# Power.net
KiCad netlist of a schematic drawn in Altium Designer
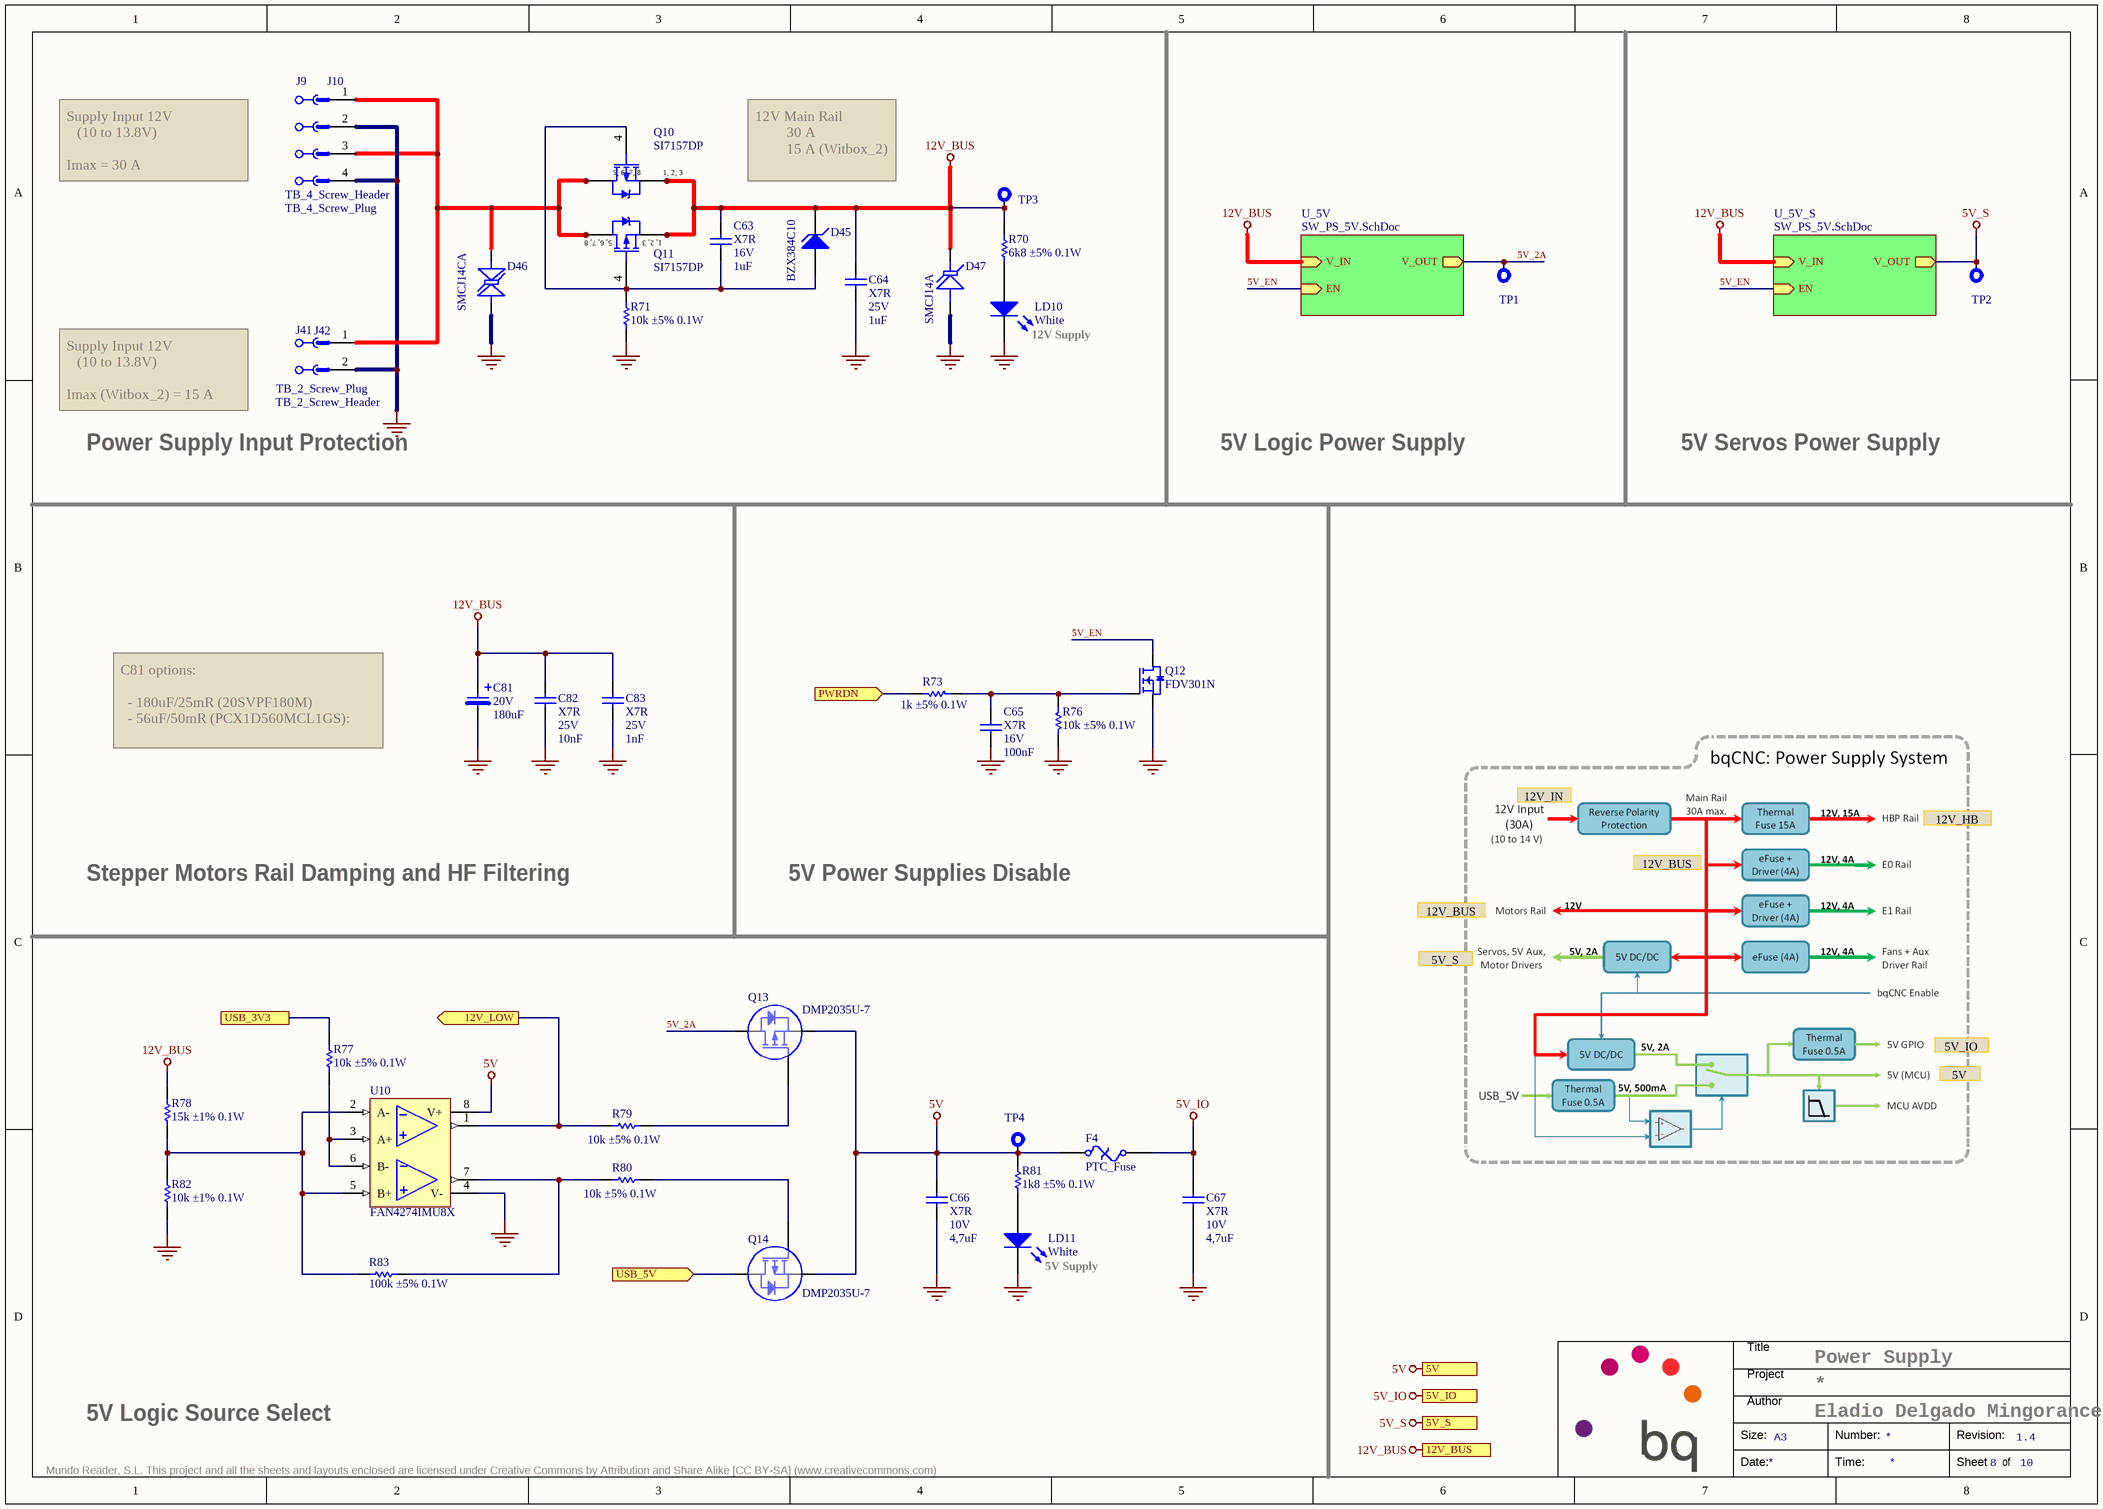
[diagram p0: Power.SchDoc]

(export (version "E")
  (design (tool "Eeschema 10.0.6"))
  (components
    (comp (ref "C63")
      (value "Capacitor")
      (footprint "C0603")
      (fields
        (field (name "DIELECTRIC") "X7R")
        (field (name "VOLTAGE") "16V")
        (field (name "CAPACITANCE") "1uF")
        (field (name "PART NUMBER") "C0603_1uF_16V_±10%_X7R")
        (field (name "TOLERANCE") "±10%")
        (field (name "MANUFACTURER") "TDK")
      )
      (libsource (lib "Pasives_Capacitor_SMD") (part "Capacitor"))
    )
    (comp (ref "C64")
      (value "Capacitor")
      (footprint "C0805")
      (fields
        (field (name "DIELECTRIC") "X7R")
        (field (name "VOLTAGE") "25V")
        (field (name "CAPACITANCE") "1uF")
        (field (name "PART NUMBER") "C0805_1uF_25V_X7R")
        (field (name "TOLERANCE") "±10%")
        (field (name "MANUFACTURER") "TDK")
      )
      (libsource (lib "Pasives_Capacitor_SMD") (part "Capacitor"))
    )
    (comp (ref "C65")
      (value "Capacitor")
      (footprint "C0603")
      (fields
        (field (name "DIELECTRIC") "X7R")
        (field (name "VOLTAGE") "16V")
        (field (name "CAPACITANCE") "100nF")
        (field (name "PART NUMBER") "C0603_100nF_16V_±10%")
        (field (name "TOLERANCE") "±10%")
        (field (name "MANUFACTURER") "Kemet")
      )
      (libsource (lib "Pasives_Capacitor_SMD") (part "Capacitor"))
    )
    (comp (ref "C66")
      (value "Capacitor")
      (footprint "C0805")
      (fields
        (field (name "DIELECTRIC") "X7R")
        (field (name "VOLTAGE") "10V")
        (field (name "CAPACITANCE") "4,7uF")
        (field (name "PART NUMBER") "C0805_4,7uF_10V_X7R")
        (field (name "TOLERANCE") "±10%")
        (field (name "MANUFACTURER") "TDK")
      )
      (libsource (lib "Pasives_Capacitor_SMD") (part "Capacitor"))
    )
    (comp (ref "C67")
      (value "Capacitor")
      (footprint "C0805")
      (fields
        (field (name "DIELECTRIC") "X7R")
        (field (name "VOLTAGE") "10V")
        (field (name "CAPACITANCE") "4,7uF")
        (field (name "PART NUMBER") "C0805_4,7uF_10V_X7R")
        (field (name "TOLERANCE") "±10%")
        (field (name "MANUFACTURER") "TDK")
      )
      (libsource (lib "Pasives_Capacitor_SMD") (part "Capacitor"))
    )
    (comp (ref "C81")
      (value "Electrolytic")
      (footprint "CASE_E7")
      (description "Capacitor, Electrolytic, SMD")
      (fields
        (field (name "VOLTAGE") "20V")
        (field (name "CAPACITANCE") "180uF")
        (field (name "PART NUMBER") "Cap_Al_180uF_20V")
        (field (name "MANUFACTURER") "Panasonic")
      )
      (libsource (lib "Pasives_Electrolytic_SMD") (part "Electrolytic"))
    )
    (comp (ref "C82")
      (value "Capacitor")
      (footprint "C0603")
      (description "Capacitor SMD")
      (fields
        (field (name "DIELECTRIC") "X7R")
        (field (name "VOLTAGE") "25V")
        (field (name "CAPACITANCE") "10nF")
        (field (name "PART NUMBER") "C0603_10nF_25V_±10%")
        (field (name "TOLERANCE") "±10%")
      )
      (libsource (lib "Pasives_Capacitor_SMD") (part "Capacitor"))
    )
    (comp (ref "C83")
      (value "Capacitor")
      (footprint "C0603")
      (description "Capacitor SMD")
      (fields
        (field (name "DIELECTRIC") "X7R")
        (field (name "VOLTAGE") "25V")
        (field (name "CAPACITANCE") "1nF")
        (field (name "PART NUMBER") "C0603_1nF_25V_±10%")
        (field (name "TOLERANCE") "±10%")
      )
      (libsource (lib "Pasives_Capacitor_SMD") (part "Capacitor"))
    )
    (comp (ref "D45")
      (value "BZX384C10")
      (footprint "SOD323")
      (description "Diode Zener")
      (fields (field (name "TOLERANCE") "0,05") (field (name "POWER") "200mW"))
      (libsource (lib "Semiconductors_Diodes") (part "Zener"))
    )
    (comp (ref "D46")
      (value "SMCJ14CA")
      (footprint "DO-214AB-SMC")
      (description "Transient Suppression Diodes Bidirectional")
      (fields (field (name "PART NUMBER") "TVS 14V Bidir SMC") (field (name "VOLTAGE") "14V"))
      (libsource (lib "Protection") (part "Zener_Bidir_TVS"))
    )
    (comp (ref "D47")
      (value "SMCJ14A")
      (footprint "DO-214AB-SMC")
      (description "Transient Suppression Diodes")
      (fields (field (name "PART NUMBER") "TVS 14V SMC") (field (name "VOLTAGE") "14V"))
      (libsource (lib "Protection") (part "Zener_TVS"))
    )
    (comp (ref "F4")
      (value "PTC_Fuse")
      (footprint "F1812")
      (description "PTC Resettable Fuse")
      (fields (field (name "PART NUMBER") "FUSE 0.5A 15V") (field (name "VOLTAGE") "15V"))
      (libsource (lib "Protection") (part "PTC_Fuse"))
    )
    (comp (ref "J9")
      (value "TB_4_Screw_Plug")
      (footprint "TB_RA_4_5.08_Plug")
      (description "Connector, Plugable Terminal  Block  - Plug 4p")
      (fields (field (name "PART NUMBER") "TB_4_RA_Plug_5.08") (field (name "MANUFACTURER") "Molex"))
      (libsource (lib "Connectors_TB") (part "TB_4_Screw_Plug"))
    )
    (comp (ref "J10")
      (value "TB_4_Screw_Header")
      (footprint "TB_RA_4_5.08")
      (description "Connector, Plugable Terminal  Block  - Header 4p")
      (fields (field (name "PART NUMBER") "TB_4_RA_Header_5.08") (field (name "MANUFACTURER") "Molex"))
      (libsource (lib "Connectors_TB") (part "TB_4_Screw_Header"))
    )
    (comp (ref "J41")
      (value "TB_2_Screw_Plug")
      (footprint "TB_RA_2_5.08_Plug")
      (description "Connector, Plugable Terminal  Block  - Plug 2p")
      (fields (field (name "PART NUMBER") "TB_2_RA_Plug_5.08") (field (name "MANUFACTURER") "Molex"))
      (libsource (lib "Connectors_TB") (part "TB_2_Screw_Plug"))
    )
    (comp (ref "J42")
      (value "TB_2_Screw_Header")
      (footprint "TB_RA_2_5.08")
      (description "Connector, Plugable Terminal  Block  - Header 2p")
      (fields (field (name "PART NUMBER") "TB_2_RA_Header_5.08") (field (name "MANUFACTURER") "Molex"))
      (libsource (lib "Connectors_TB") (part "TB_2_Screw_Header"))
    )
    (comp (ref "LD10")
      (value "White")
      (footprint "LED0603")
      (description "LED")
      (fields (field (name "PART NUMBER") "LW Q38G-Q2R3") (field (name "MANUFACTURER") "OSRAM Opto"))
      (libsource (lib "Optoelectronics") (part "LED"))
    )
    (comp (ref "LD11")
      (value "White")
      (footprint "LED0603")
      (description "LED")
      (fields (field (name "PART NUMBER") "LW Q38G-Q2R3") (field (name "MANUFACTURER") "OSRAM Opto"))
      (libsource (lib "Optoelectronics") (part "LED"))
    )
    (comp (ref "Q10")
      (value "SI7157DP")
      (footprint "AO_DFN5x6")
      (description "PFET Power SO8")
      (fields (field (name "MANUFACTURER") "Vishay"))
      (libsource (lib "Semiconductors_Transistors") (part "P-MOSFET Power SO8"))
    )
    (comp (ref "Q11")
      (value "SI7157DP")
      (footprint "AO_DFN5x6")
      (description "PFET Power SO8")
      (fields (field (name "MANUFACTURER") "Vishay"))
      (libsource (lib "Semiconductors_Transistors") (part "P-MOSFET Power SO8"))
    )
    (comp (ref "Q12")
      (value "FDV301N")
      (footprint "SOT23-3")
      (description "Mosfet Channel N Enhancement Mode")
      (fields (field (name "MANUFACTURER") "Fairchild Semiconductor"))
      (libsource (lib "Semiconductors_Transistors") (part "Mosfet_N"))
    )
    (comp (ref "Q13")
      (value "DMP2035U-7")
      (footprint "SOT23-3")
      (description "Mosfet Channel P Enhancement Mode")
      (fields (field (name "PART NUMBER") "DMP2035U") (field (name "MANUFACTURER") "Diodes Incorporated"))
      (libsource (lib "Semiconductors_Transistors") (part "Mosfet_P"))
    )
    (comp (ref "Q14")
      (value "DMP2035U-7")
      (footprint "SOT23-3")
      (description "Mosfet Channel P Enhancement Mode")
      (fields (field (name "PART NUMBER") "DMP2035U") (field (name "MANUFACTURER") "Diodes Incorporated"))
      (libsource (lib "Semiconductors_Transistors") (part "Mosfet_P"))
    )
    (comp (ref "R70")
      (value "6k8 ±5% 0.1W")
      (footprint "R0603")
      (description "Resistor, SMD")
      (fields (field (name "TOLERANCE") "±5%") (field (name "POWER") "0.1W"))
      (libsource (lib "Pasives_Resistor_SMD") (part "Resistor"))
    )
    (comp (ref "R71")
      (value "10k ±5% 0.1W")
      (footprint "R0603")
      (description "Resistor")
      (fields (field (name "TOLERANCE") "±5%") (field (name "POWER") "0.1W"))
      (libsource (lib "Pasives_Resistor_SMD") (part "Resistor"))
    )
    (comp (ref "R73")
      (value "1k ±5% 0.1W")
      (footprint "R0603")
      (description "Resistor")
      (fields (field (name "TOLERANCE") "±5%") (field (name "POWER") "0.1W"))
      (libsource (lib "Pasives_Resistor_SMD") (part "Resistor"))
    )
    (comp (ref "R76")
      (value "10k ±5% 0.1W")
      (footprint "R0603")
      (description "Resistor")
      (fields (field (name "TOLERANCE") "±5%") (field (name "POWER") "0.1W"))
      (libsource (lib "Pasives_Resistor_SMD") (part "Resistor"))
    )
    (comp (ref "R77")
      (value "10k ±5% 0.1W")
      (footprint "R0603")
      (description "Resistor")
      (fields (field (name "TOLERANCE") "±5%") (field (name "POWER") "0.1W"))
      (libsource (lib "Pasives_Resistor_SMD") (part "Resistor"))
    )
    (comp (ref "R78")
      (value "15k ±1% 0.1W")
      (footprint "R0603")
      (description "Resistor")
      (fields (field (name "TOLERANCE") "±1%") (field (name "POWER") "0.1W"))
      (libsource (lib "Pasives_Resistor_SMD") (part "Resistor"))
    )
    (comp (ref "R79")
      (value "10k ±5% 0.1W")
      (footprint "R0603")
      (description "Resistor")
      (fields (field (name "TOLERANCE") "±5%") (field (name "POWER") "0.1W"))
      (libsource (lib "Pasives_Resistor_SMD") (part "Resistor"))
    )
    (comp (ref "R80")
      (value "10k ±5% 0.1W")
      (footprint "R0603")
      (description "Resistor")
      (fields (field (name "TOLERANCE") "±5%") (field (name "POWER") "0.1W"))
      (libsource (lib "Pasives_Resistor_SMD") (part "Resistor"))
    )
    (comp (ref "R81")
      (value "1k8 ±5% 0.1W")
      (footprint "R0603")
      (description "Resistor, SMD")
      (fields (field (name "TOLERANCE") "±5%") (field (name "POWER") "0.1W"))
      (libsource (lib "Pasives_Resistor_SMD") (part "Resistor"))
    )
    (comp (ref "R82")
      (value "10k ±1% 0.1W")
      (footprint "R0603")
      (description "Resistor")
      (fields (field (name "TOLERANCE") "±1%") (field (name "POWER") "0.1W"))
      (libsource (lib "Pasives_Resistor_SMD") (part "Resistor"))
    )
    (comp (ref "R83")
      (value "100k ±5% 0.1W")
      (footprint "R0603")
      (description "Resistor")
      (fields (field (name "TOLERANCE") "±5%") (field (name "POWER") "0.1W"))
      (libsource (lib "Pasives_Resistor_SMD") (part "Resistor"))
    )
    (comp (ref "TP1")
      (value "Testpoint")
      (footprint "TP_SMD_1mm")
      (fields (field (name "PART NUMBER") "TP_SMD_1mm"))
      (libsource (lib "Miscelanea") (part "Testpoint"))
    )
    (comp (ref "TP2")
      (value "Testpoint")
      (footprint "TP_SMD_1mm")
      (fields (field (name "PART NUMBER") "TP_SMD_1mm"))
      (libsource (lib "Miscelanea") (part "Testpoint"))
    )
    (comp (ref "TP3")
      (value "Testpoint")
      (footprint "TP_SMD_1mm")
      (fields (field (name "PART NUMBER") "TP_SMD_1mm"))
      (libsource (lib "Miscelanea") (part "Testpoint"))
    )
    (comp (ref "TP4")
      (value "Testpoint")
      (footprint "TP_SMD_1mm")
      (fields (field (name "PART NUMBER") "TP_SMD_1mm"))
      (libsource (lib "Miscelanea") (part "Testpoint"))
    )
    (comp (ref "U10")
      (value "FAN4274IMU8X")
      (footprint "VSSOP8")
      (description "Operational Amplifier Dual 3.7MHz")
      (fields (field (name "PART NUMBER") "FAN4274") (field (name "MANUFACTURER") "Fairchild Semiconductor"))
      (libsource (lib "Semiconductors_OA") (part "FAN4274"))
    )
  )
  (nets
    (net (code "1") (name "/5V_2A") (class "Default")
      (node (ref "Q13") (pin "3") (pinfunction "D_3") (pintype "passive"))
      (node (ref "TP1") (pin "1") (pinfunction "1_1") (pintype "passive"))
    )
    (net (code "2") (name "/5V_EN") (class "Default")
      (node (ref "Q12") (pin "3") (pinfunction "D_3") (pintype "passive"))
    )
    (net (code "3") (name "/12V_LOW") (class "Default")
      (node (ref "R79") (pin "2") (pinfunction "2_2") (pintype "passive"))
      (node (ref "U10") (pin "1") (pinfunction "OutA_1") (pintype "output"))
    )
    (net (code "4") (name "/PWRDN") (class "Default")
      (node (ref "R73") (pin "2") (pinfunction "2_2") (pintype "passive"))
    )
    (net (code "5") (name "/USB_3V3") (class "Default")
      (node (ref "R77") (pin "2") (pinfunction "2_2") (pintype "passive"))
    )
    (net (code "6") (name "/USB_5V") (class "Default")
      (node (ref "Q14") (pin "3") (pinfunction "D_3") (pintype "passive"))
    )
    (net (code "7") (name "5V") (class "Default")
      (node (ref "C66") (pin "2") (pinfunction "2_2") (pintype "passive"))
      (node (ref "F4") (pin "1") (pinfunction "1_1") (pintype "passive"))
      (node (ref "Q13") (pin "2") (pinfunction "S_2") (pintype "passive"))
      (node (ref "Q14") (pin "2") (pinfunction "S_2") (pintype "passive"))
      (node (ref "R81") (pin "2") (pinfunction "2_2") (pintype "passive"))
      (node (ref "TP4") (pin "1") (pinfunction "1_1") (pintype "passive"))
      (node (ref "U10") (pin "8") (pinfunction "V+_8") (pintype "power_in"))
    )
    (net (code "8") (name "5V_IO") (class "Default")
      (node (ref "C67") (pin "2") (pinfunction "2_2") (pintype "passive"))
      (node (ref "F4") (pin "2") (pinfunction "2_2") (pintype "passive"))
    )
    (net (code "9") (name "5V_S") (class "Default")
      (node (ref "TP2") (pin "1") (pinfunction "1_1") (pintype "passive"))
    )
    (net (code "10") (name "12V_BUS") (class "Default")
      (node (ref "C63") (pin "2") (pinfunction "2_2") (pintype "passive"))
      (node (ref "C64") (pin "2") (pinfunction "2_2") (pintype "passive"))
      (node (ref "C81") (pin "1") (pinfunction "1_1") (pintype "passive"))
      (node (ref "C82") (pin "2") (pinfunction "2_2") (pintype "passive"))
      (node (ref "C83") (pin "2") (pinfunction "2_2") (pintype "passive"))
      (node (ref "D45") (pin "k") (pinfunction "K_k") (pintype "passive"))
      (node (ref "D47") (pin "K") (pinfunction "K_K") (pintype "passive"))
      (node (ref "Q10") (pin "1") (pinfunction "S_1") (pintype "passive"))
      (node (ref "Q10") (pin "2") (pinfunction "S_2") (pintype "passive"))
      (node (ref "Q10") (pin "3") (pinfunction "S_3") (pintype "passive"))
      (node (ref "Q11") (pin "1") (pinfunction "S_1") (pintype "passive"))
      (node (ref "Q11") (pin "2") (pinfunction "S_2") (pintype "passive"))
      (node (ref "Q11") (pin "3") (pinfunction "S_3") (pintype "passive"))
      (node (ref "R70") (pin "2") (pinfunction "2_2") (pintype "passive"))
      (node (ref "R78") (pin "2") (pinfunction "2_2") (pintype "passive"))
      (node (ref "TP3") (pin "1") (pinfunction "1_1") (pintype "passive"))
    )
    (net (code "11") (name "GND") (class "Default")
      (node (ref "C64") (pin "1") (pinfunction "1_1") (pintype "passive"))
      (node (ref "C65") (pin "1") (pinfunction "1_1") (pintype "passive"))
      (node (ref "C66") (pin "1") (pinfunction "1_1") (pintype "passive"))
      (node (ref "C67") (pin "1") (pinfunction "1_1") (pintype "passive"))
      (node (ref "C81") (pin "2") (pinfunction "2_2") (pintype "passive"))
      (node (ref "C82") (pin "1") (pinfunction "1_1") (pintype "passive"))
      (node (ref "C83") (pin "1") (pinfunction "1_1") (pintype "passive"))
      (node (ref "D46") (pin "A") (pinfunction "A_A") (pintype "passive"))
      (node (ref "D47") (pin "A") (pinfunction "A_A") (pintype "passive"))
      (node (ref "J10") (pin "2") (pinfunction "2_2") (pintype "passive"))
      (node (ref "J10") (pin "4") (pinfunction "4_4") (pintype "passive"))
      (node (ref "J42") (pin "2") (pinfunction "2_2") (pintype "passive"))
      (node (ref "LD10") (pin "K") (pinfunction "K_K") (pintype "passive"))
      (node (ref "LD11") (pin "K") (pinfunction "K_K") (pintype "passive"))
      (node (ref "Q12") (pin "2") (pinfunction "S_2") (pintype "passive"))
      (node (ref "R71") (pin "1") (pinfunction "1_1") (pintype "passive"))
      (node (ref "R76") (pin "2") (pinfunction "2_2") (pintype "passive"))
      (node (ref "R82") (pin "1") (pinfunction "1_1") (pintype "passive"))
      (node (ref "U10") (pin "4") (pinfunction "V-_4") (pintype "power_in"))
    )
    (net (code "12") (name "Net-(D46-PadK)") (class "Default")
      (node (ref "D46") (pin "K") (pinfunction "K_K") (pintype "passive"))
      (node (ref "J10") (pin "1") (pinfunction "1_1") (pintype "passive"))
      (node (ref "J10") (pin "3") (pinfunction "3_3") (pintype "passive"))
      (node (ref "J42") (pin "1") (pinfunction "1_1") (pintype "passive"))
      (node (ref "Q10") (pin "5") (pinfunction "D_5") (pintype "passive"))
      (node (ref "Q10") (pin "6") (pinfunction "D_6") (pintype "passive"))
      (node (ref "Q10") (pin "7") (pinfunction "D_7") (pintype "passive"))
      (node (ref "Q10") (pin "8") (pinfunction "D_8") (pintype "passive"))
      (node (ref "Q11") (pin "5") (pinfunction "D_5") (pintype "passive"))
      (node (ref "Q11") (pin "6") (pinfunction "D_6") (pintype "passive"))
      (node (ref "Q11") (pin "7") (pinfunction "D_7") (pintype "passive"))
      (node (ref "Q11") (pin "8") (pinfunction "D_8") (pintype "passive"))
    )
    (net (code "13") (name "Net-(LD10-PadA)") (class "Default")
      (node (ref "LD10") (pin "A") (pinfunction "A_A") (pintype "passive"))
      (node (ref "R70") (pin "1") (pinfunction "1_1") (pintype "passive"))
    )
    (net (code "14") (name "Net-(LD11-PadA)") (class "Default")
      (node (ref "LD11") (pin "A") (pinfunction "A_A") (pintype "passive"))
      (node (ref "R81") (pin "1") (pinfunction "1_1") (pintype "passive"))
    )
    (net (code "15") (name "Net-(Q10-G)") (class "Default")
      (node (ref "C63") (pin "1") (pinfunction "1_1") (pintype "passive"))
      (node (ref "D45") (pin "A") (pinfunction "A_A") (pintype "passive"))
      (node (ref "Q10") (pin "4") (pinfunction "G_4") (pintype "passive"))
      (node (ref "Q11") (pin "4") (pinfunction "G_4") (pintype "passive"))
      (node (ref "R71") (pin "2") (pinfunction "2_2") (pintype "passive"))
    )
    (net (code "16") (name "Net-(Q12-G)") (class "Default")
      (node (ref "C65") (pin "2") (pinfunction "2_2") (pintype "passive"))
      (node (ref "Q12") (pin "1") (pinfunction "G_1") (pintype "passive"))
      (node (ref "R73") (pin "1") (pinfunction "1_1") (pintype "passive"))
      (node (ref "R76") (pin "1") (pinfunction "1_1") (pintype "passive"))
    )
    (net (code "17") (name "Net-(Q13-G)") (class "Default")
      (node (ref "Q13") (pin "1") (pinfunction "G_1") (pintype "passive"))
      (node (ref "R79") (pin "1") (pinfunction "1_1") (pintype "passive"))
    )
    (net (code "18") (name "Net-(Q14-G)") (class "Default")
      (node (ref "Q14") (pin "1") (pinfunction "G_1") (pintype "passive"))
      (node (ref "R80") (pin "1") (pinfunction "1_1") (pintype "passive"))
    )
    (net (code "19") (name "Net-(U10-A+)") (class "Default")
      (node (ref "R77") (pin "1") (pinfunction "1_1") (pintype "passive"))
      (node (ref "U10") (pin "3") (pinfunction "A+_3") (pintype "input"))
      (node (ref "U10") (pin "6") (pinfunction "B-_6") (pintype "input"))
    )
    (net (code "20") (name "Net-(U10-A-)") (class "Default")
      (node (ref "R78") (pin "1") (pinfunction "1_1") (pintype "passive"))
      (node (ref "R82") (pin "2") (pinfunction "2_2") (pintype "passive"))
      (node (ref "R83") (pin "1") (pinfunction "1_1") (pintype "passive"))
      (node (ref "U10") (pin "2") (pinfunction "A-_2") (pintype "input"))
      (node (ref "U10") (pin "5") (pinfunction "B+_5") (pintype "input"))
    )
    (net (code "21") (name "Net-(U10-OutB)") (class "Default")
      (node (ref "R80") (pin "2") (pinfunction "2_2") (pintype "passive"))
      (node (ref "R83") (pin "2") (pinfunction "2_2") (pintype "passive"))
      (node (ref "U10") (pin "7") (pinfunction "OutB_7") (pintype "output"))
    )
  )
)
